# -MCU.net
KiCad netlist of a schematic drawn in Altium Designer
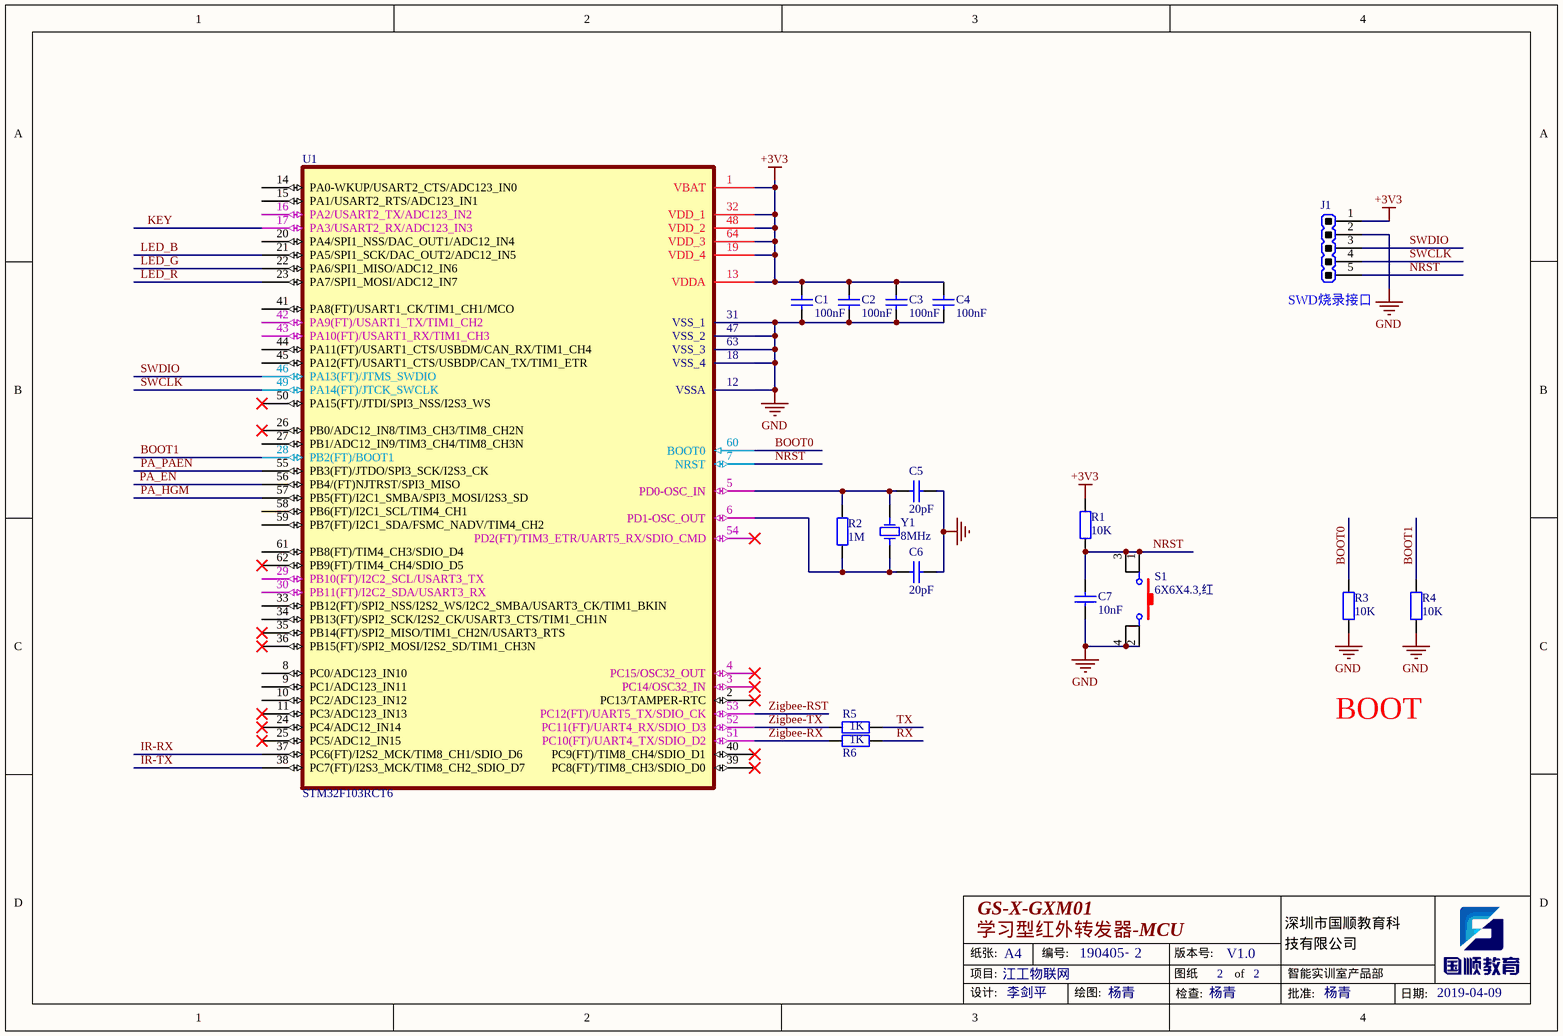
[diagram p0: 学习型红外转发器-MCU.SchDoc]

(export (version "E")
  (design (tool "Eeschema 10.0.6"))
  (components
    (comp (ref "C1")
      (value "100nF")
      (footprint "C0603")
      (description "Capacitor")
      (libsource (lib "贴片电容") (part "100nF_50V_0603"))
    )
    (comp (ref "C2")
      (value "100nF")
      (footprint "C0603")
      (description "Capacitor")
      (libsource (lib "贴片电容") (part "100nF_50V_0603"))
    )
    (comp (ref "C3")
      (value "100nF")
      (footprint "C0603")
      (description "Capacitor")
      (libsource (lib "贴片电容") (part "100nF_50V_0603"))
    )
    (comp (ref "C4")
      (value "100nF")
      (footprint "C0603")
      (description "Capacitor")
      (libsource (lib "贴片电容") (part "100nF_50V_0603"))
    )
    (comp (ref "C5")
      (value "20pF")
      (footprint "C0603")
      (description "Capacitor")
      (libsource (lib "贴片电容") (part "20pF_50V_0603"))
    )
    (comp (ref "C6")
      (value "20pF")
      (footprint "C0603")
      (description "Capacitor")
      (libsource (lib "贴片电容") (part "20pF_50V_0603"))
    )
    (comp (ref "C7")
      (value "10nF")
      (footprint "C0603")
      (description "Capacitor")
      (libsource (lib "贴片电容") (part "10nF_16V_0603"))
    )
    (comp (ref "J1")
      (value "HDRM-2.54/11-1*5P-AK")
      (footprint "HDRM-2.54-1*5P-AK")
      (description "排针,直")
      (libsource (lib "接口") (part "HDRM-2.54/11-1*5P-AK"))
    )
    (comp (ref "R1")
      (value "10K")
      (footprint "R0603")
      (description "10K,±5%,0603")
      (libsource (lib "贴片电阻") (part "10K_5%_0603"))
    )
    (comp (ref "R2")
      (value "1M")
      (footprint "R0603")
      (description "1M,±5%,0603")
      (libsource (lib "贴片电阻") (part "1M_5%_0603"))
    )
    (comp (ref "R3")
      (value "10K")
      (footprint "R0603")
      (description "10K,±5%,0603")
      (libsource (lib "贴片电阻") (part "10K_5%_0603"))
    )
    (comp (ref "R4")
      (value "10K")
      (footprint "R0603")
      (description "10K,±5%,0603")
      (libsource (lib "贴片电阻") (part "10K_5%_0603"))
    )
    (comp (ref "R5")
      (value "1K")
      (footprint "R0603")
      (description "1K,±5%,0603")
      (libsource (lib "贴片电阻") (part "1K_5%_0603"))
    )
    (comp (ref "R6")
      (value "1K")
      (footprint "R0603")
      (description "1K,±5%,0603")
      (libsource (lib "贴片电阻") (part "1K_5%_0603"))
    )
    (comp (ref "S1")
      (value "6X6X4.3,红")
      (footprint "SW2-6.0X6.0X4.3-R-SMD")
      (description "6X6X4.3,红,贴片")
      (libsource (lib "6x6轻触开关") (part "SW-PB_6X6X4.3-4P-R-SMD"))
    )
    (comp (ref "U1")
      (value "STM32F103RCT6")
      (footprint "LQFP64")
      (libsource (lib "IC") (part "STM32F103RCT6-LQFP64_1"))
    )
    (comp (ref "Y1")
      (value "8MHz")
      (footprint "X_HC49-S")
      (description "8MHz,HC-49S")
      (libsource (lib "杂项元件") (part "CRYSTAL_8M_HC49S"))
    )
  )
  (nets
    (net (code "1") (name "+3V3") (class "Default")
      (node (ref "C1") (pin "1") (pinfunction "1_1") (pintype "passive"))
      (node (ref "C2") (pin "2") (pinfunction "2_2") (pintype "passive"))
      (node (ref "C3") (pin "2") (pinfunction "2_2") (pintype "passive"))
      (node (ref "C4") (pin "2") (pinfunction "2_2") (pintype "passive"))
      (node (ref "J1") (pin "1") (pinfunction "1_1") (pintype "passive"))
      (node (ref "R1") (pin "1") (pinfunction "1_1") (pintype "passive"))
      (node (ref "U1") (pin "1") (pinfunction "VBAT_1") (pintype "power_in"))
      (node (ref "U1") (pin "13") (pinfunction "VDDA_13") (pintype "power_in"))
      (node (ref "U1") (pin "19") (pinfunction "VDD_4_19") (pintype "power_in"))
      (node (ref "U1") (pin "32") (pinfunction "VDD_1_32") (pintype "power_in"))
      (node (ref "U1") (pin "48") (pinfunction "VDD_2_48") (pintype "power_in"))
      (node (ref "U1") (pin "64") (pinfunction "VDD_3_64") (pintype "power_in"))
    )
    (net (code "2") (name "/BOOT0") (class "Default")
      (node (ref "R3") (pin "1") (pinfunction "1_1") (pintype "passive"))
      (node (ref "U1") (pin "60") (pinfunction "BOOT0_60") (pintype "input"))
    )
    (net (code "3") (name "/BOOT1") (class "Default")
      (node (ref "R4") (pin "1") (pinfunction "1_1") (pintype "passive"))
      (node (ref "U1") (pin "28") (pinfunction "PB2(FT)/BOOT1_28") (pintype "bidirectional"))
    )
    (net (code "4") (name "/IR-RX") (class "Default")
      (node (ref "U1") (pin "37") (pinfunction "PC6(FT)/I2S2_MCK/TIM8_CH1/SDIO_D6_37") (pintype "bidirectional"))
    )
    (net (code "5") (name "/IR-TX") (class "Default")
      (node (ref "U1") (pin "38") (pinfunction "PC7(FT)/I2S3_MCK/TIM8_CH2_SDIO_D7_38") (pintype "bidirectional"))
    )
    (net (code "6") (name "/KEY") (class "Default")
      (node (ref "U1") (pin "17") (pinfunction "PA3/USART2_RX/ADC123_IN3_17") (pintype "bidirectional"))
    )
    (net (code "7") (name "/LED_B") (class "Default")
      (node (ref "U1") (pin "21") (pinfunction "PA5/SPI1_SCK/DAC_OUT2/ADC12_IN5_21") (pintype "bidirectional"))
    )
    (net (code "8") (name "/LED_G") (class "Default")
      (node (ref "U1") (pin "22") (pinfunction "PA6/SPI1_MISO/ADC12_IN6_22") (pintype "bidirectional"))
    )
    (net (code "9") (name "/LED_R") (class "Default")
      (node (ref "U1") (pin "23") (pinfunction "PA7/SPI1_MOSI/ADC12_IN7_23") (pintype "bidirectional"))
    )
    (net (code "10") (name "/NRST") (class "Default")
      (node (ref "C7") (pin "2") (pinfunction "2_2") (pintype "passive"))
      (node (ref "J1") (pin "5") (pinfunction "5_5") (pintype "passive"))
      (node (ref "R1") (pin "2") (pinfunction "2_2") (pintype "passive"))
      (node (ref "S1") (pin "1") (pinfunction "1_1") (pintype "passive"))
      (node (ref "S1") (pin "3") (pinfunction "3_3") (pintype "passive"))
      (node (ref "U1") (pin "7") (pinfunction "NRST_7") (pintype "bidirectional"))
    )
    (net (code "11") (name "/PA_EN") (class "Default")
      (node (ref "U1") (pin "56") (pinfunction "PB4/(FT)NJTRST/SPI3_MISO_56") (pintype "bidirectional"))
    )
    (net (code "12") (name "/PA_HGM") (class "Default")
      (node (ref "U1") (pin "57") (pinfunction "PB5(FT)/I2C1_SMBA/SPI3_MOSI/I2S3_SD_57") (pintype "bidirectional"))
    )
    (net (code "13") (name "/PA_PAEN") (class "Default")
      (node (ref "U1") (pin "55") (pinfunction "PB3(FT)/JTDO/SPI3_SCK/I2S3_CK_55") (pintype "bidirectional"))
    )
    (net (code "14") (name "/RX") (class "Default")
      (node (ref "R6") (pin "1") (pinfunction "1_1") (pintype "passive"))
    )
    (net (code "15") (name "/SWCLK") (class "Default")
      (node (ref "J1") (pin "4") (pinfunction "4_4") (pintype "passive"))
      (node (ref "U1") (pin "49") (pinfunction "PA14(FT)/JTCK_SWCLK_49") (pintype "bidirectional"))
    )
    (net (code "16") (name "/SWDIO") (class "Default")
      (node (ref "J1") (pin "3") (pinfunction "3_3") (pintype "passive"))
      (node (ref "U1") (pin "46") (pinfunction "PA13(FT)/JTMS_SWDIO_46") (pintype "bidirectional"))
    )
    (net (code "17") (name "/TX") (class "Default")
      (node (ref "R5") (pin "1") (pinfunction "1_1") (pintype "passive"))
    )
    (net (code "18") (name "/Zigbee-RST") (class "Default")
      (node (ref "U1") (pin "53") (pinfunction "PC12(FT)/UART5_TX/SDIO_CK_53") (pintype "bidirectional"))
    )
    (net (code "19") (name "/Zigbee-RX") (class "Default")
      (node (ref "R6") (pin "2") (pinfunction "2_2") (pintype "passive"))
      (node (ref "U1") (pin "51") (pinfunction "PC10(FT)/UART4_TX/SDIO_D2_51") (pintype "bidirectional"))
    )
    (net (code "20") (name "/Zigbee-TX") (class "Default")
      (node (ref "R5") (pin "2") (pinfunction "2_2") (pintype "passive"))
      (node (ref "U1") (pin "52") (pinfunction "PC11(FT)/UART4_RX/SDIO_D3_52") (pintype "bidirectional"))
    )
    (net (code "21") (name "GND") (class "Default")
      (node (ref "C1") (pin "2") (pinfunction "2_2") (pintype "passive"))
      (node (ref "C2") (pin "1") (pinfunction "1_1") (pintype "passive"))
      (node (ref "C3") (pin "1") (pinfunction "1_1") (pintype "passive"))
      (node (ref "C4") (pin "1") (pinfunction "1_1") (pintype "passive"))
      (node (ref "C5") (pin "2") (pinfunction "2_2") (pintype "passive"))
      (node (ref "C6") (pin "2") (pinfunction "2_2") (pintype "passive"))
      (node (ref "C7") (pin "1") (pinfunction "1_1") (pintype "passive"))
      (node (ref "J1") (pin "2") (pinfunction "2_2") (pintype "passive"))
      (node (ref "R3") (pin "2") (pinfunction "2_2") (pintype "passive"))
      (node (ref "R4") (pin "2") (pinfunction "2_2") (pintype "passive"))
      (node (ref "S1") (pin "2") (pinfunction "2_2") (pintype "passive"))
      (node (ref "S1") (pin "4") (pinfunction "4_4") (pintype "passive"))
      (node (ref "U1") (pin "12") (pinfunction "VSSA_12") (pintype "power_in"))
      (node (ref "U1") (pin "18") (pinfunction "VSS_4_18") (pintype "power_in"))
      (node (ref "U1") (pin "31") (pinfunction "VSS_1_31") (pintype "power_in"))
      (node (ref "U1") (pin "47") (pinfunction "VSS_2_47") (pintype "power_in"))
      (node (ref "U1") (pin "63") (pinfunction "VSS_3_63") (pintype "power_in"))
    )
    (net (code "22") (name "Net-(U1-PD0-OSC_IN)") (class "Default")
      (node (ref "C5") (pin "1") (pinfunction "1_1") (pintype "passive"))
      (node (ref "R2") (pin "2") (pinfunction "2_2") (pintype "passive"))
      (node (ref "U1") (pin "5") (pinfunction "PD0-OSC_IN_5") (pintype "bidirectional"))
      (node (ref "Y1") (pin "2") (pinfunction "2_2") (pintype "passive"))
    )
    (net (code "23") (name "Net-(U1-PD1-OSC_OUT)") (class "Default")
      (node (ref "C6") (pin "1") (pinfunction "1_1") (pintype "passive"))
      (node (ref "R2") (pin "1") (pinfunction "1_1") (pintype "passive"))
      (node (ref "U1") (pin "6") (pinfunction "PD1-OSC_OUT_6") (pintype "bidirectional"))
      (node (ref "Y1") (pin "1") (pinfunction "1_1") (pintype "passive"))
    )
    (net (code "24") (name "unconnected-(U1-PA0-WKUP{slash}USART2_CTS{slash}ADC123_IN0-Pad14)") (class "Default")
      (node (ref "U1") (pin "14") (pinfunction "PA0-WKUP/USART2_CTS/ADC123_IN0_14") (pintype "bidirectional"))
    )
    (net (code "25") (name "unconnected-(U1-PA1{slash}USART2_RTS{slash}ADC123_IN1-Pad15)") (class "Default")
      (node (ref "U1") (pin "15") (pinfunction "PA1/USART2_RTS/ADC123_IN1_15") (pintype "bidirectional"))
    )
    (net (code "26") (name "unconnected-(U1-PA2{slash}USART2_TX{slash}ADC123_IN2-Pad16)") (class "Default")
      (node (ref "U1") (pin "16") (pinfunction "PA2/USART2_TX/ADC123_IN2_16") (pintype "bidirectional"))
    )
    (net (code "27") (name "unconnected-(U1-PA4{slash}SPI1_NSS{slash}DAC_OUT1{slash}ADC12_IN4-Pad20)") (class "Default")
      (node (ref "U1") (pin "20") (pinfunction "PA4/SPI1_NSS/DAC_OUT1/ADC12_IN4_20") (pintype "bidirectional"))
    )
    (net (code "28") (name "unconnected-(U1-PA8(FT){slash}USART1_CK{slash}TIM1_CH1{slash}MCO-Pad41)") (class "Default")
      (node (ref "U1") (pin "41") (pinfunction "PA8(FT)/USART1_CK/TIM1_CH1/MCO_41") (pintype "bidirectional"))
    )
    (net (code "29") (name "unconnected-(U1-PA9(FT){slash}USART1_TX{slash}TIM1_CH2-Pad42)") (class "Default")
      (node (ref "U1") (pin "42") (pinfunction "PA9(FT)/USART1_TX/TIM1_CH2_42") (pintype "bidirectional"))
    )
    (net (code "30") (name "unconnected-(U1-PA10(FT){slash}USART1_RX{slash}TIM1_CH3-Pad43)") (class "Default")
      (node (ref "U1") (pin "43") (pinfunction "PA10(FT)/USART1_RX/TIM1_CH3_43") (pintype "bidirectional"))
    )
    (net (code "31") (name "unconnected-(U1-PA11(FT){slash}USART1_CTS{slash}USBDM{slash}CAN_RX{slash}TIM1_CH4-Pad44)") (class "Default")
      (node (ref "U1") (pin "44") (pinfunction "PA11(FT)/USART1_CTS/USBDM/CAN_RX/TIM1_CH4_44") (pintype "bidirectional"))
    )
    (net (code "32") (name "unconnected-(U1-PA12(FT){slash}USART1_CTS{slash}USBDP{slash}CAN_TX{slash}TIM1_ETR-Pad45)") (class "Default")
      (node (ref "U1") (pin "45") (pinfunction "PA12(FT)/USART1_CTS/USBDP/CAN_TX/TIM1_ETR_45") (pintype "bidirectional"))
    )
    (net (code "33") (name "unconnected-(U1-PA15(FT){slash}JTDI{slash}SPI3_NSS{slash}I2S3_WS-Pad50)") (class "Default")
      (node (ref "U1") (pin "50") (pinfunction "PA15(FT)/JTDI/SPI3_NSS/I2S3_WS_50") (pintype "bidirectional+no_connect"))
    )
    (net (code "34") (name "unconnected-(U1-PB0{slash}ADC12_IN8{slash}TIM3_CH3{slash}TIM8_CH2N-Pad26)") (class "Default")
      (node (ref "U1") (pin "26") (pinfunction "PB0/ADC12_IN8/TIM3_CH3/TIM8_CH2N_26") (pintype "bidirectional+no_connect"))
    )
    (net (code "35") (name "unconnected-(U1-PB1{slash}ADC12_IN9{slash}TIM3_CH4{slash}TIM8_CH3N-Pad27)") (class "Default")
      (node (ref "U1") (pin "27") (pinfunction "PB1/ADC12_IN9/TIM3_CH4/TIM8_CH3N_27") (pintype "bidirectional"))
    )
    (net (code "36") (name "unconnected-(U1-PB6(FT){slash}I2C1_SCL{slash}TIM4_CH1-Pad58)") (class "Default")
      (node (ref "U1") (pin "58") (pinfunction "PB6(FT)/I2C1_SCL/TIM4_CH1_58") (pintype "bidirectional"))
    )
    (net (code "37") (name "unconnected-(U1-PB7(FT){slash}I2C1_SDA{slash}FSMC_NADV{slash}TIM4_CH2-Pad59)") (class "Default")
      (node (ref "U1") (pin "59") (pinfunction "PB7(FT)/I2C1_SDA/FSMC_NADV/TIM4_CH2_59") (pintype "bidirectional"))
    )
    (net (code "38") (name "unconnected-(U1-PB8(FT){slash}TIM4_CH3{slash}SDIO_D4-Pad61)") (class "Default")
      (node (ref "U1") (pin "61") (pinfunction "PB8(FT)/TIM4_CH3/SDIO_D4_61") (pintype "bidirectional"))
    )
    (net (code "39") (name "unconnected-(U1-PB9(FT){slash}TIM4_CH4{slash}SDIO_D5-Pad62)") (class "Default")
      (node (ref "U1") (pin "62") (pinfunction "PB9(FT)/TIM4_CH4/SDIO_D5_62") (pintype "bidirectional+no_connect"))
    )
    (net (code "40") (name "unconnected-(U1-PB10(FT){slash}I2C2_SCL{slash}USART3_TX-Pad29)") (class "Default")
      (node (ref "U1") (pin "29") (pinfunction "PB10(FT)/I2C2_SCL/USART3_TX_29") (pintype "bidirectional"))
    )
    (net (code "41") (name "unconnected-(U1-PB11(FT){slash}I2C2_SDA{slash}USART3_RX-Pad30)") (class "Default")
      (node (ref "U1") (pin "30") (pinfunction "PB11(FT)/I2C2_SDA/USART3_RX_30") (pintype "bidirectional"))
    )
    (net (code "42") (name "unconnected-(U1-PB12(FT){slash}SPI2_NSS{slash}I2S2_WS{slash}I2C2_SMBA{slash}USART3_CK{slash}TIM1_BKIN-Pad33)") (class "Default")
      (node (ref "U1") (pin "33") (pinfunction "PB12(FT)/SPI2_NSS/I2S2_WS/I2C2_SMBA/USART3_CK/TIM1_BKIN_33") (pintype "bidirectional"))
    )
    (net (code "43") (name "unconnected-(U1-PB13(FT){slash}SPI2_SCK{slash}I2S2_CK{slash}USART3_CTS{slash}TIM1_CH1N-Pad34)") (class "Default")
      (node (ref "U1") (pin "34") (pinfunction "PB13(FT)/SPI2_SCK/I2S2_CK/USART3_CTS/TIM1_CH1N_34") (pintype "bidirectional"))
    )
    (net (code "44") (name "unconnected-(U1-PB14(FT){slash}SPI2_MISO{slash}TIM1_CH2N{slash}USART3_RTS-Pad35)") (class "Default")
      (node (ref "U1") (pin "35") (pinfunction "PB14(FT)/SPI2_MISO/TIM1_CH2N/USART3_RTS_35") (pintype "bidirectional+no_connect"))
    )
    (net (code "45") (name "unconnected-(U1-PB15(FT){slash}SPI2_MOSI{slash}I2S2_SD{slash}TIM1_CH3N-Pad36)") (class "Default")
      (node (ref "U1") (pin "36") (pinfunction "PB15(FT)/SPI2_MOSI/I2S2_SD/TIM1_CH3N_36") (pintype "bidirectional+no_connect"))
    )
    (net (code "46") (name "unconnected-(U1-PC0{slash}ADC123_IN10-Pad8)") (class "Default")
      (node (ref "U1") (pin "8") (pinfunction "PC0/ADC123_IN10_8") (pintype "bidirectional"))
    )
    (net (code "47") (name "unconnected-(U1-PC1{slash}ADC123_IN11-Pad9)") (class "Default")
      (node (ref "U1") (pin "9") (pinfunction "PC1/ADC123_IN11_9") (pintype "bidirectional"))
    )
    (net (code "48") (name "unconnected-(U1-PC2{slash}ADC123_IN12-Pad10)") (class "Default")
      (node (ref "U1") (pin "10") (pinfunction "PC2/ADC123_IN12_10") (pintype "bidirectional"))
    )
    (net (code "49") (name "unconnected-(U1-PC3{slash}ADC123_IN13-Pad11)") (class "Default")
      (node (ref "U1") (pin "11") (pinfunction "PC3/ADC123_IN13_11") (pintype "bidirectional+no_connect"))
    )
    (net (code "50") (name "unconnected-(U1-PC4{slash}ADC12_IN14-Pad24)") (class "Default")
      (node (ref "U1") (pin "24") (pinfunction "PC4/ADC12_IN14_24") (pintype "bidirectional+no_connect"))
    )
    (net (code "51") (name "unconnected-(U1-PC5{slash}ADC12_IN15-Pad25)") (class "Default")
      (node (ref "U1") (pin "25") (pinfunction "PC5/ADC12_IN15_25") (pintype "bidirectional+no_connect"))
    )
    (net (code "52") (name "unconnected-(U1-PC8(FT){slash}TIM8_CH3{slash}SDIO_D0-Pad39)") (class "Default")
      (node (ref "U1") (pin "39") (pinfunction "PC8(FT)/TIM8_CH3/SDIO_D0_39") (pintype "bidirectional+no_connect"))
    )
    (net (code "53") (name "unconnected-(U1-PC9(FT){slash}TIM8_CH4{slash}SDIO_D1-Pad40)") (class "Default")
      (node (ref "U1") (pin "40") (pinfunction "PC9(FT)/TIM8_CH4/SDIO_D1_40") (pintype "bidirectional+no_connect"))
    )
    (net (code "54") (name "unconnected-(U1-PC13{slash}TAMPER-RTC-Pad2)") (class "Default")
      (node (ref "U1") (pin "2") (pinfunction "PC13/TAMPER-RTC_2") (pintype "bidirectional+no_connect"))
    )
    (net (code "55") (name "unconnected-(U1-PC14{slash}OSC32_IN-Pad3)") (class "Default")
      (node (ref "U1") (pin "3") (pinfunction "PC14/OSC32_IN_3") (pintype "bidirectional+no_connect"))
    )
    (net (code "56") (name "unconnected-(U1-PC15{slash}OSC32_OUT-Pad4)") (class "Default")
      (node (ref "U1") (pin "4") (pinfunction "PC15/OSC32_OUT_4") (pintype "bidirectional+no_connect"))
    )
    (net (code "57") (name "unconnected-(U1-PD2(FT){slash}TIM3_ETR{slash}UART5_RX{slash}SDIO_CMD-Pad54)") (class "Default")
      (node (ref "U1") (pin "54") (pinfunction "PD2(FT)/TIM3_ETR/UART5_RX/SDIO_CMD_54") (pintype "bidirectional+no_connect"))
    )
  )
)
